# DataDriven_sheet2_nRF9160.net
KiCad netlist of a schematic drawn in Altium Designer
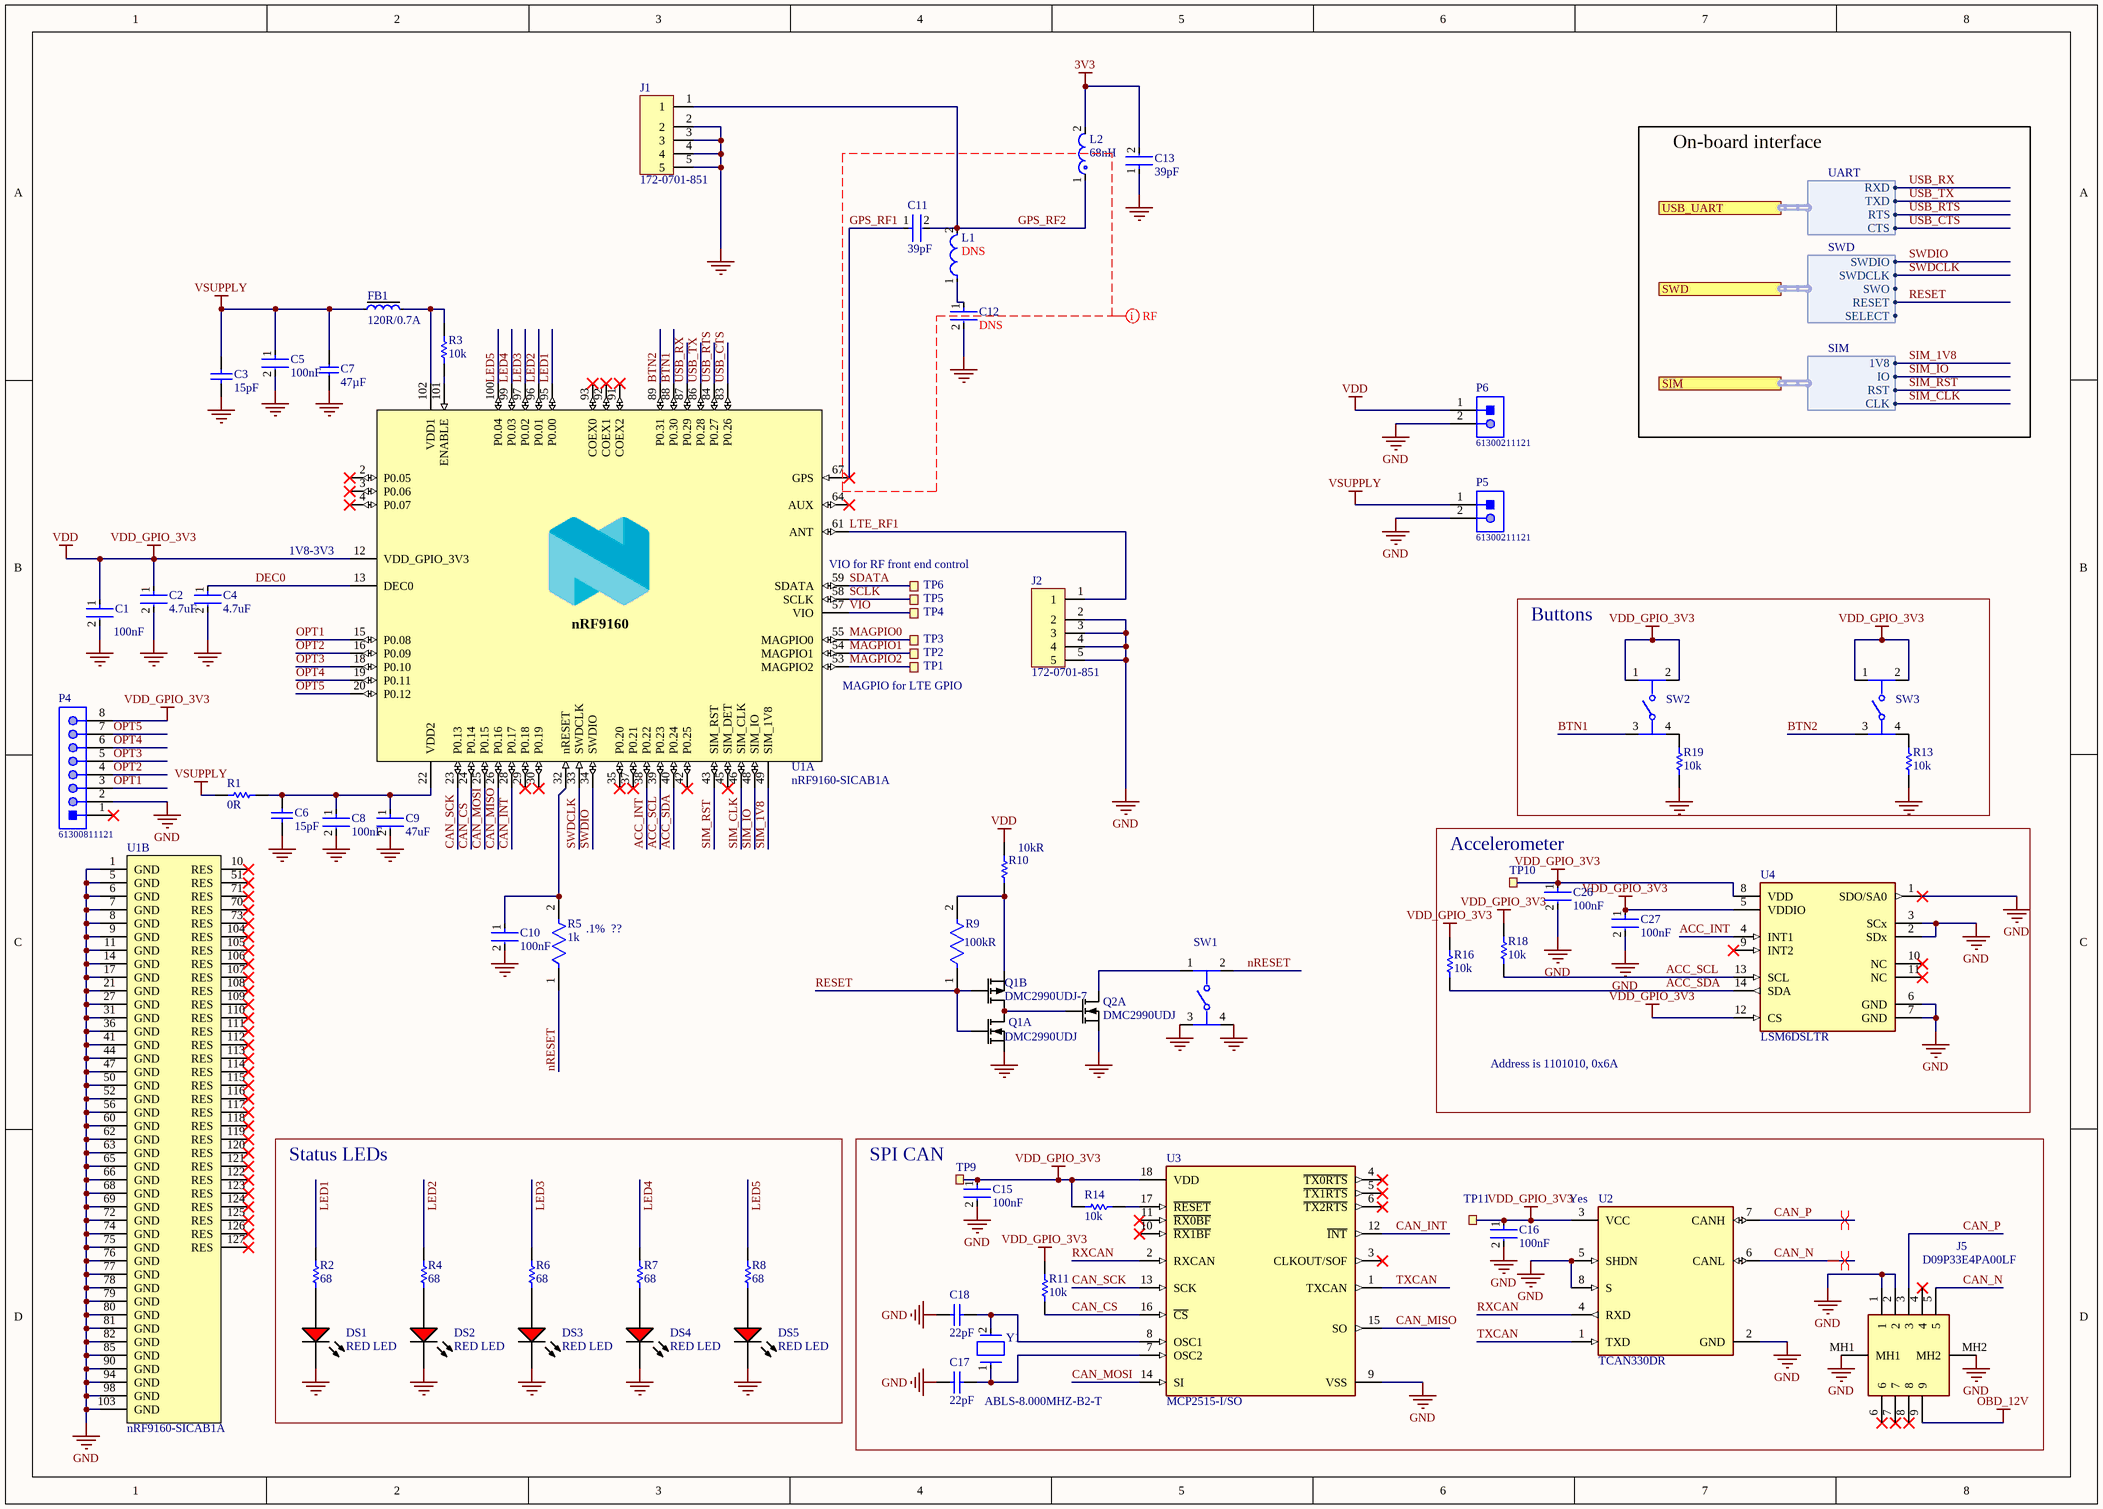
[diagram p0: DataDriven_sheet2_nRF9160.SchDoc]

(export (version "E")
  (design (tool "Eeschema 10.0.6"))
  (components
    (comp (ref "C1")
      (value "100nF")
      (footprint "FP-CGA3E-0_3-0_1-IPC_A")
      (description "Cap Ceramic 100nF 50V X7R 10% Pad SMD 0603 +125°C Automotive T/R")
      (fields (field (name "TOLERANCE") "10%") (field (name "VOLTAGE") "50V"))
      (libsource (lib "Altium Content Vault") (part "b4654b650e69147ec39a6b967a45e02"))
    )
    (comp (ref "C2")
      (value "4.7uF")
      (footprint "FP-C0603-CG-MFG")
      (description "CAP CER 4.7UF 6.3V X5R 0603")
      (fields (field (name "TOLERANCE") "10%") (field (name "MANUFACTURER") "Kemet"))
      (libsource (lib "Altium Content Vault") (part "11868f565c42a9108669ba33697ecf6"))
    )
    (comp (ref "C3")
      (value "15pF")
      (footprint "CAPC1608X90X35ML10T15")
      (description "15 pF ±5% 50V Ceramic Capacitor C0G, NP0 0603 (1608 Metric)")
      (fields (field (name "PART NUMBER") "GRM1885C1H150JA01D") (field (name "MANUFACTURER") "Murata"))
      (libsource (lib "Altium Content Vault") (part "CAP"))
    )
    (comp (ref "C4")
      (value "4.7uF")
      (footprint "FP-C0603-CG-MFG")
      (description "CAP CER 4.7UF 6.3V X5R 0603")
      (fields (field (name "TOLERANCE") "10%") (field (name "MANUFACTURER") "Kemet"))
      (libsource (lib "Altium Content Vault") (part "11868f565c42a9108669ba33697ecf6"))
    )
    (comp (ref "C5")
      (value "100nF")
      (footprint "FP-CGA3E-0_3-0_1-IPC_A")
      (description "Cap Ceramic 100nF 50V X7R 10% Pad SMD 0603 +125°C Automotive T/R")
      (fields (field (name "TOLERANCE") "10%") (field (name "VOLTAGE") "50V"))
      (libsource (lib "Altium Content Vault") (part "b4654b650e69147ec39a6b967a45e02"))
    )
    (comp (ref "C6")
      (value "15pF")
      (footprint "CAPC1608X90X35ML10T15")
      (description "15 pF ±5% 50V Ceramic Capacitor C0G, NP0 0603 (1608 Metric)")
      (fields (field (name "PART NUMBER") "GRM1885C1H150JA01D") (field (name "MANUFACTURER") "Murata"))
      (libsource (lib "Altium Content Vault") (part "CAP"))
    )
    (comp (ref "C7")
      (value "47µF")
      (footprint "pca10090:CAPC2012X11L")
      (description "CAP CER 47UF 10V X5R 0805")
      (fields
        (field (name "PART NUMBER") "C0805-47µ-10V")
        (field (name "MANUFACTURER") "Murata")
        (field (name "AUTHOR") "rsk")
      )
      (libsource (lib "AltiumLib") (part "CAP"))
    )
    (comp (ref "C8")
      (value "100nF")
      (footprint "FP-CGA3E-0_3-0_1-IPC_A")
      (description "Cap Ceramic 100nF 50V X7R 10% Pad SMD 0603 +125°C Automotive T/R")
      (fields (field (name "TOLERANCE") "10%") (field (name "VOLTAGE") "50V"))
      (libsource (lib "Altium Content Vault") (part "b4654b650e69147ec39a6b967a45e02"))
    )
    (comp (ref "C9")
      (value "47uF")
      (footprint "FP-GRM188-0_2-IPC_B")
      (description "Chip Multilayer Ceramic Capacitors for General Purpose, 0603, 47uF, X5R, 15%, 20%, 6.3V")
      (fields (field (name "TOLERANCE") "20%") (field (name "PART NUMBER") "GRM188R60J476ME15D"))
      (libsource (lib "Altium Content Vault") (part "11868f565c42a9108669ba33697ecf6"))
    )
    (comp (ref "C10")
      (value "100nF")
      (footprint "FP-CGA3E-0_3-0_1-IPC_A")
      (description "Cap Ceramic 100nF 50V X7R 10% Pad SMD 0603 +125°C Automotive T/R")
      (fields (field (name "TOLERANCE") "10%") (field (name "VOLTAGE") "50V"))
      (libsource (lib "Altium Content Vault") (part "b4654b650e69147ec39a6b967a45e02"))
    )
    (comp (ref "C11")
      (value "39pF")
      (footprint "FP-C0603C-CF-MFG")
      (description "CAP CER 39PF 50V 5% NP0 0603")
      (fields
        (field (name "OCTOPART") "https://octopart.com/c0603c390j5gactu-kemet-8375739")
        (field (name "MANUFACTURER PART NUMBER") "C0603C390J5GACTU")
      )
      (libsource (lib "Altium Content Vault") (part "b4654b650e69147ec39a6b967a45e02"))
    )
    (comp (ref "C12")
      (value "DNS")
      (footprint "FP-CGA3E-0_3-0_1-IPC_A")
      (description "Cap Ceramic 100nF 50V X7R 10% Pad SMD 0603 +125°C Automotive T/R")
      (fields (field (name "TOLERANCE") "10%") (field (name "VOLTAGE") "50V"))
      (libsource (lib "Altium Content Vault") (part "b4654b650e69147ec39a6b967a45e02"))
    )
    (comp (ref "C13")
      (value "39pF")
      (footprint "FP-C0603C-CF-MFG")
      (description "CAP CER 39PF 50V 5% NP0 0603")
      (fields
        (field (name "OCTOPART") "https://octopart.com/c0603c390j5gactu-kemet-8375739")
        (field (name "MANUFACTURER PART NUMBER") "C0603C390J5GACTU")
      )
      (libsource (lib "Altium Content Vault") (part "b4654b650e69147ec39a6b967a45e02"))
    )
    (comp (ref "C15")
      (value "100nF")
      (footprint "FP-CGA3E-0_3-0_1-IPC_A")
      (description "Cap Ceramic 100nF 50V X7R 10% Pad SMD 0603 +125°C Automotive T/R")
      (fields (field (name "TOLERANCE") "10%") (field (name "VOLTAGE") "50V"))
      (libsource (lib "Altium Content Vault") (part "b4654b650e69147ec39a6b967a45e02"))
    )
    (comp (ref "C16")
      (value "100nF")
      (footprint "FP-CGA3E-0_3-0_1-IPC_A")
      (description "Cap Ceramic 100nF 50V X7R 10% Pad SMD 0603 +125°C Automotive T/R")
      (fields (field (name "TOLERANCE") "10%") (field (name "VOLTAGE") "50V"))
      (libsource (lib "Altium Content Vault") (part "b4654b650e69147ec39a6b967a45e02"))
    )
    (comp (ref "C17")
      (value "22pF")
      (footprint "CAPC1608X90X35ML10T15")
      (description "Chip Capacitor, 22 pF, +/- 5%, 50 V, -55 to 125 degC, 0603 (1608 Metric), RoHS, Tape and Reel")
      (fields
        (field (name "MANUFACTURER") "Murata")
        (field (name "MANUFACTURER PART NUMBER") "GRM1885C1H220JA01D")
      )
      (libsource (lib "Altium Content Vault") (part "CAP-NP-2"))
    )
    (comp (ref "C18")
      (value "22pF")
      (footprint "CAPC1608X90X35ML10T15")
      (description "Chip Capacitor, 22 pF, +/- 5%, 50 V, -55 to 125 degC, 0603 (1608 Metric), RoHS, Tape and Reel")
      (fields
        (field (name "MANUFACTURER") "Murata")
        (field (name "MANUFACTURER PART NUMBER") "GRM1885C1H220JA01D")
      )
      (libsource (lib "Altium Content Vault") (part "CAP-NP-2"))
    )
    (comp (ref "C26")
      (value "100nF")
      (footprint "FP-CGA3E-0_3-0_1-IPC_A")
      (description "Cap Ceramic 100nF 50V X7R 10% Pad SMD 0603 +125°C Automotive T/R")
      (fields (field (name "TOLERANCE") "10%") (field (name "VOLTAGE") "50V"))
      (libsource (lib "Altium Content Vault") (part "b4654b650e69147ec39a6b967a45e02"))
    )
    (comp (ref "C27")
      (value "100nF")
      (footprint "FP-CGA3E-0_3-0_1-IPC_A")
      (description "Cap Ceramic 100nF 50V X7R 10% Pad SMD 0603 +125°C Automotive T/R")
      (fields (field (name "TOLERANCE") "10%") (field (name "VOLTAGE") "50V"))
      (libsource (lib "Altium Content Vault") (part "b4654b650e69147ec39a6b967a45e02"))
    )
    (comp (ref "DS1")
      (value "RED LED")
      (footprint "VISH-TLMX1100_V")
      (description "LED, RED, 2.1 V, -40 to 100 degC, 2-Pin SMD (0603), RoHS, Tape and Reel")
      (fields (field (name "TOLERANCE") "5%") (field (name "PART NUMBER") "TLMS1100-GS08"))
      (libsource (lib "Altium Content Vault") (part "LED-RED-AK-2"))
    )
    (comp (ref "DS2")
      (value "RED LED")
      (footprint "VISH-TLMX1100_V")
      (description "LED, RED, 2.1 V, -40 to 100 degC, 2-Pin SMD (0603), RoHS, Tape and Reel")
      (fields (field (name "TOLERANCE") "5%") (field (name "MANUFACTURER") "Vishay"))
      (libsource (lib "Altium Content Vault") (part "LED-RED-AK-2"))
    )
    (comp (ref "DS3")
      (value "RED LED")
      (footprint "VISH-TLMX1100_V")
      (description "LED, RED, 2.1 V, -40 to 100 degC, 2-Pin SMD (0603), RoHS, Tape and Reel")
      (fields (field (name "TOLERANCE") "5%") (field (name "MANUFACTURER") "Vishay"))
      (libsource (lib "Altium Content Vault") (part "LED-RED-AK-2"))
    )
    (comp (ref "DS4")
      (value "RED LED")
      (footprint "VISH-TLMX1100_V")
      (description "LED, RED, 2.1 V, -40 to 100 degC, 2-Pin SMD (0603), RoHS, Tape and Reel")
      (fields (field (name "TOLERANCE") "5%") (field (name "MANUFACTURER") "Vishay"))
      (libsource (lib "Altium Content Vault") (part "LED-RED-AK-2"))
    )
    (comp (ref "DS5")
      (value "RED LED")
      (footprint "VISH-TLMX1100_V")
      (description "LED, RED, 2.1 V, -40 to 100 degC, 2-Pin SMD (0603), RoHS, Tape and Reel")
      (fields (field (name "TOLERANCE") "5%") (field (name "MANUFACTURER") "Vishay"))
      (libsource (lib "Altium Content Vault") (part "LED-RED-AK-2"))
    )
    (comp (ref "FB1")
      (value "120R/0.7A")
      (footprint "pca10090:INDC1005X04L")
      (description "Ferrite Bead, 120 Ohm @ 100MHz, 700mA, 130 mOhm Max")
      (fields
        (field (name "PART NUMBER") "FB0402-120R@100M-700mA")
        (field (name "MANUFACTURER") "Murata")
        (field (name "AUTHOR") "rsk")
      )
      (libsource (lib "AltiumLib") (part "IND_F"))
    )
    (comp (ref "J1")
      (value "172-0701-851")
      (footprint "DataDriven_PCB1:142-0701-851")
      (description "SMA Connector Jack, Female Socket 50Ohm Board Edge, End Launch Solder Tab")
      (fields
        (field (name "MANUFACTURER") "Cinch Connectivity Solutions Johnson")
        (field (name "MANUFACTURER PART NUMBER") "142-0701-851")
      )
      (libsource (lib "DataDriven") (part "172-0701-851"))
    )
    (comp (ref "J2")
      (value "172-0701-851")
      (footprint "DataDriven_PCB1:142-0701-851")
      (description "SMA Connector Jack, Female Socket 50Ohm Board Edge, End Launch Solder Tab")
      (fields
        (field (name "MANUFACTURER") "Cinch Connectivity Solutions Johnson")
        (field (name "MANUFACTURER PART NUMBER") "142-0701-851")
      )
      (libsource (lib "DataDriven") (part "172-0701-851"))
    )
    (comp (ref "J5")
      (value "D09P33E4PA00LF")
      (footprint "DataDriven_PCB1:D09P33E4PA00LF")
      (description "D-Sub Standard Connectors 9P RA PIN SOLDER SHELL SIZE E")
      (fields
        (field (name "MOUSER PART NUMBER") "649-D09P33E4PA00LF")
        (field (name "MANUFACTURER") "Amphenol FCI")
      )
      (libsource (lib "DataDriven") (part "D09P33E4PA00LF"))
    )
    (comp (ref "L1")
      (value "DNS")
      (footprint "FP-LQW18AN_00-MFG")
      (description "Wire Wound RF Inductor 9.1nH ±0.5nH 650mA 0.11Ω 0603 (1608)")
      (fields (field (name "TOLERANCE") "5%") (field (name "MANUFACTURER") "Murata"))
      (libsource (lib "Altium Content Vault") (part "725321dda6339637d4d059423bc1c3c"))
    )
    (comp (ref "L2")
      (value "68nH")
      (footprint "FP-LQG18HH_00-MFG")
      (description "Multilayer type RF Inductor 68nH ±5% 0.8Ω 400mA 0603")
      (fields (field (name "TOLERANCE") "5%") (field (name "MANUFACTURER") "Murata"))
      (libsource (lib "Altium Content Vault") (part "4cc4b267dca4c8e51f7102f422741d8"))
    )
    (comp (ref "P4")
      (value "61300811121")
      (footprint "61300811121")
      (description "THT Vertical Pin Header WR-PHD, Pitch 2.54 mm, Single Row, 8 pins")
      (fields (field (name "MANUFACTURER") "Wurth Elektronik") (field (name "PUBLISHER") "WurthElektronik"))
      (libsource (lib "Altium Content Vault") (part "WE-CN-1P-M-R8"))
    )
    (comp (ref "P5")
      (value "61300211121")
      (footprint "61300211121")
      (description "THT Vertical Pin Header WR-PHD, Pitch 2.54 mm, Single Row, 2 pins")
      (fields (field (name "MANUFACTURER") "Wurth Elektronik") (field (name "PUBLISHER") "WurthElektronik"))
      (libsource (lib "Altium Content Vault") (part "WE-CN-1P-M-R2"))
    )
    (comp (ref "P6")
      (value "61300211121")
      (footprint "61300211121")
      (description "THT Vertical Pin Header WR-PHD, Pitch 2.54 mm, Single Row, 2 pins")
      (fields (field (name "MANUFACTURER") "Wurth Elektronik") (field (name "PUBLISHER") "WurthElektronik"))
      (libsource (lib "Altium Content Vault") (part "WE-CN-1P-M-R2"))
    )
    (comp (ref "Q1")
      (value "DMC2990UDJ")
      (footprint "pca10090:SOTFL35P100X50-6N")
      (description "MOSFET, Dual N and P-Channel, 20V, 450mA/310mA, 990mOhm, 350mW")
      (fields
        (field (name "PART NUMBER") "DMC2990UDJ-7")
        (field (name "MANUFACTURER") "Diodes Incorporated")
        (field (name "AUTHOR") "rsk")
      )
      (libsource (lib "AltiumLib") (part "T{colon}FET-N/P-DUAL"))
    )
    (comp (ref "Q2")
      (value "DMC2990UDJ")
      (footprint "pca10090:SOTFL35P100X50-6N")
      (description "MOSFET, Dual N and P-Channel, 20V, 450mA/310mA, 990mOhm, 350mW")
      (fields
        (field (name "PART NUMBER") "DMC2990UDJ-7")
        (field (name "MANUFACTURER") "Diodes Incorporated")
        (field (name "AUTHOR") "rsk")
      )
      (libsource (lib "AltiumLib") (part "T{colon}FET-N/P-DUAL"))
    )
    (comp (ref "R1")
      (value "0R")
      (footprint "RESC1608X55X25ML10T15")
      (description "Chip Resistor, 0 Ohm, +/- 5%, 0.1 W, -55 to 155 degC, 0603 (1608 Metric), RoHS, Tape and Reel")
      (fields (field (name "TOLERANCE") "5%") (field (name "MANUFACTURER") "Yageo"))
      (libsource (lib "Altium Content Vault") (part "RES-2"))
    )
    (comp (ref "R2")
      (value "68")
      (footprint "RESC1608X55X30ML15T15")
      (description "68 Ohms ±1% 0.1W, 1/10W Chip Resistor 0603 (1608 Metric) Automotive AEC-Q200 Thick Film")
      (fields (field (name "MANUFACTURER") "Panasonic") (field (name "PART NUMBER") "ERJ-3EKF68R0V"))
      (libsource (lib "Altium Content Vault") (part "RES"))
    )
    (comp (ref "R3")
      (value "10k")
      (footprint "RESC1609X50X30NL8T20")
      (description "Chip Resistor, 10 KOhm, +/- 1%, 100 mW, -55 to 155 degC, 0603 (1608 Metric), RoHS, Tape and Reel")
      (fields
        (field (name "MANUFACTURER") "Vishay Semiconductor")
        (field (name "MANUFACTURER PART NUMBER") "CRCW060310K0FKEA")
      )
      (libsource (lib "Altium Content Vault") (part "RES-2"))
    )
    (comp (ref "R4")
      (value "68")
      (footprint "RESC1608X55X30ML15T15")
      (description "68 Ohms ±1% 0.1W, 1/10W Chip Resistor 0603 (1608 Metric) Automotive AEC-Q200 Thick Film")
      (fields (field (name "MANUFACTURER") "Panasonic") (field (name "PART NUMBER") "ERJ-3EKF68R0V"))
      (libsource (lib "Altium Content Vault") (part "RES"))
    )
    (comp (ref "R5")
      (value "1k")
      (footprint "FP-ERA3A-IPC_C")
      (description "RES SMD 1K OHM 0.1% 1/10W 0603")
      (fields (field (name "TOLERANCE") "0.1%") (field (name "MANUFACTURER") "Panasonic"))
      (libsource (lib "Altium Content Vault") (part "1029c3af85768c4190bb7ad29bc67b5"))
    )
    (comp (ref "R6")
      (value "68")
      (footprint "RESC1608X55X30ML15T15")
      (description "68 Ohms ±1% 0.1W, 1/10W Chip Resistor 0603 (1608 Metric) Automotive AEC-Q200 Thick Film")
      (fields (field (name "MANUFACTURER") "Panasonic") (field (name "PART NUMBER") "ERJ-3EKF68R0V"))
      (libsource (lib "Altium Content Vault") (part "RES"))
    )
    (comp (ref "R7")
      (value "68")
      (footprint "RESC1608X55X30ML15T15")
      (description "68 Ohms ±1% 0.1W, 1/10W Chip Resistor 0603 (1608 Metric) Automotive AEC-Q200 Thick Film")
      (fields (field (name "MANUFACTURER") "Panasonic") (field (name "PART NUMBER") "ERJ-3EKF68R0V"))
      (libsource (lib "Altium Content Vault") (part "RES"))
    )
    (comp (ref "R8")
      (value "68")
      (footprint "RESC1608X55X30ML15T15")
      (description "68 Ohms ±1% 0.1W, 1/10W Chip Resistor 0603 (1608 Metric) Automotive AEC-Q200 Thick Film")
      (fields (field (name "MANUFACTURER") "Panasonic") (field (name "PART NUMBER") "ERJ-3EKF68R0V"))
      (libsource (lib "Altium Content Vault") (part "RES"))
    )
    (comp (ref "R9")
      (value "RC0603FR-07100KL")
      (footprint "FP-RC0603-0_55-MFG")
      (description "RES SMD 100K OHM 1% 1/10W 0603")
      (fields
        (field (name "RESISTANCE") "100kR")
        (field (name "TOLERANCE") "1%")
        (field (name "MANUFACTURER") "Yaego")
      )
      (libsource (lib "Altium Content Vault") (part "1029c3af85768c4190bb7ad29bc67b5"))
    )
    (comp (ref "R10")
      (value "10kR")
      (footprint "RESC1609X50X30NL8T20")
      (description "Chip Resistor, 10 KOhm, +/- 1%, 100 mW, -55 to 155 degC, 0603 (1608 Metric), RoHS, Tape and Reel")
      (fields (field (name "MANUFACTURER") "Vishay Semiconductor") (field (name "TOLERANCE") "1%"))
      (libsource (lib "Altium Content Vault") (part "RES-2"))
    )
    (comp (ref "R11")
      (value "10k")
      (footprint "RESC1609X50X30NL8T20")
      (description "Chip Resistor, 10 KOhm, +/- 1%, 100 mW, -55 to 155 degC, 0603 (1608 Metric), RoHS, Tape and Reel")
      (fields
        (field (name "MANUFACTURER") "Vishay Semiconductor")
        (field (name "MANUFACTURER PART NUMBER") "CRCW060310K0FKEA")
      )
      (libsource (lib "Altium Content Vault") (part "RES-2"))
    )
    (comp (ref "R13")
      (value "10k")
      (footprint "RESC1609X50X30NL8T20")
      (description "Chip Resistor, 10 KOhm, +/- 1%, 100 mW, -55 to 155 degC, 0603 (1608 Metric), RoHS, Tape and Reel")
      (fields
        (field (name "MANUFACTURER") "Vishay Semiconductor")
        (field (name "MANUFACTURER PART NUMBER") "CRCW060310K0FKEA")
      )
      (libsource (lib "Altium Content Vault") (part "RES-2"))
    )
    (comp (ref "R14")
      (value "10k")
      (footprint "RESC1609X50X30NL8T20")
      (description "Chip Resistor, 10 KOhm, +/- 1%, 100 mW, -55 to 155 degC, 0603 (1608 Metric), RoHS, Tape and Reel")
      (fields
        (field (name "MANUFACTURER") "Vishay Semiconductor")
        (field (name "MANUFACTURER PART NUMBER") "CRCW060310K0FKEA")
      )
      (libsource (lib "Altium Content Vault") (part "RES-2"))
    )
    (comp (ref "R16")
      (value "10k")
      (footprint "RESC1609X50X30NL8T20")
      (description "Chip Resistor, 10 KOhm, +/- 1%, 100 mW, -55 to 155 degC, 0603 (1608 Metric), RoHS, Tape and Reel")
      (fields
        (field (name "MANUFACTURER") "Vishay Semiconductor")
        (field (name "MANUFACTURER PART NUMBER") "CRCW060310K0FKEA")
      )
      (libsource (lib "Altium Content Vault") (part "RES-2"))
    )
    (comp (ref "R18")
      (value "10k")
      (footprint "RESC1609X50X30NL8T20")
      (description "Chip Resistor, 10 KOhm, +/- 1%, 100 mW, -55 to 155 degC, 0603 (1608 Metric), RoHS, Tape and Reel")
      (fields
        (field (name "MANUFACTURER") "Vishay Semiconductor")
        (field (name "MANUFACTURER PART NUMBER") "CRCW060310K0FKEA")
      )
      (libsource (lib "Altium Content Vault") (part "RES-2"))
    )
    (comp (ref "R19")
      (value "10k")
      (footprint "RESC1609X50X30NL8T20")
      (description "Chip Resistor, 10 KOhm, +/- 1%, 100 mW, -55 to 155 degC, 0603 (1608 Metric), RoHS, Tape and Reel")
      (fields
        (field (name "MANUFACTURER") "Vishay Semiconductor")
        (field (name "MANUFACTURER PART NUMBER") "CRCW060310K0FKEA")
      )
      (libsource (lib "Altium Content Vault") (part "RES-2"))
    )
    (comp (ref "SW1")
      (value "~")
      (footprint "FP-PTS645SM43SMTR92LFS-MFG")
      (description "SWITCH TACTILE SPST-NO 0.05A 12V")
      (fields
        (field (name "MANUFACTURER") "ITT C&K")
        (field (name "MANUFACTURER PART NUMBER") "PTS645SM43SMTR92LFS")
      )
      (libsource (lib "Altium Content Vault") (part "1adf0dd01260c80cf25a44bfd6b99ba"))
    )
    (comp (ref "SW2")
      (value "~")
      (footprint "FP-PTS645SM43SMTR92LFS-MFG")
      (description "SWITCH TACTILE SPST-NO 0.05A 12V")
      (fields
        (field (name "MANUFACTURER") "ITT C&K")
        (field (name "MANUFACTURER PART NUMBER") "PTS645SM43SMTR92LFS")
      )
      (libsource (lib "Altium Content Vault") (part "1adf0dd01260c80cf25a44bfd6b99ba"))
    )
    (comp (ref "SW3")
      (value "~")
      (footprint "FP-PTS645SM43SMTR92LFS-MFG")
      (description "SWITCH TACTILE SPST-NO 0.05A 12V")
      (fields
        (field (name "MANUFACTURER") "ITT C&K")
        (field (name "MANUFACTURER PART NUMBER") "PTS645SM43SMTR92LFS")
      )
      (libsource (lib "Altium Content Vault") (part "1adf0dd01260c80cf25a44bfd6b99ba"))
    )
    (comp (ref "TP1")
      (value "Ø1.0mm,SMD")
      (footprint "pca10090:TP_SMD_D1.0mm")
      (description "1.0mm circular SMD testpad")
      (fields
        (field (name "PART NUMBER") "TP_SMD_Ø1.0MM")
        (field (name "MANUFACTURER") "Nordic Semiconductor")
        (field (name "AUTHOR") "rsk")
      )
      (libsource (lib "AltiumLib") (part "TESTPAD"))
    )
    (comp (ref "TP2")
      (value "Ø1.0mm,SMD")
      (footprint "pca10090:TP_SMD_D1.0mm")
      (description "1.0mm circular SMD testpad")
      (fields
        (field (name "PART NUMBER") "TP_SMD_Ø1.0MM")
        (field (name "MANUFACTURER") "Nordic Semiconductor")
        (field (name "AUTHOR") "rsk")
      )
      (libsource (lib "AltiumLib") (part "TESTPAD"))
    )
    (comp (ref "TP3")
      (value "Ø1.0mm,SMD")
      (footprint "pca10090:TP_SMD_D1.0mm")
      (description "1.0mm circular SMD testpad")
      (fields
        (field (name "PART NUMBER") "TP_SMD_Ø1.0MM")
        (field (name "MANUFACTURER") "Nordic Semiconductor")
        (field (name "AUTHOR") "rsk")
      )
      (libsource (lib "AltiumLib") (part "TESTPAD"))
    )
    (comp (ref "TP4")
      (value "Ø1.0mm,SMD")
      (footprint "pca10090:TP_SMD_D1.0mm")
      (description "1.0mm circular SMD testpad")
      (fields
        (field (name "PART NUMBER") "TP_SMD_Ø1.0MM")
        (field (name "MANUFACTURER") "Nordic Semiconductor")
        (field (name "AUTHOR") "rsk")
      )
      (libsource (lib "AltiumLib") (part "TESTPAD"))
    )
    (comp (ref "TP5")
      (value "Ø1.0mm,SMD")
      (footprint "pca10090:TP_SMD_D1.0mm")
      (description "1.0mm circular SMD testpad")
      (fields
        (field (name "PART NUMBER") "TP_SMD_Ø1.0MM")
        (field (name "MANUFACTURER") "Nordic Semiconductor")
        (field (name "AUTHOR") "rsk")
      )
      (libsource (lib "AltiumLib") (part "TESTPAD"))
    )
    (comp (ref "TP6")
      (value "Ø1.0mm,SMD")
      (footprint "pca10090:TP_SMD_D1.0mm")
      (description "1.0mm circular SMD testpad")
      (fields
        (field (name "PART NUMBER") "TP_SMD_Ø1.0MM")
        (field (name "MANUFACTURER") "Nordic Semiconductor")
        (field (name "AUTHOR") "rsk")
      )
      (libsource (lib "AltiumLib") (part "TESTPAD"))
    )
    (comp (ref "TP9")
      (value "Ø1.0mm,SMD")
      (footprint "pca10090:TP_SMD_D1.0mm")
      (description "1.0mm circular SMD testpad")
      (fields
        (field (name "PART NUMBER") "TP_SMD_Ø1.0MM")
        (field (name "MANUFACTURER") "Nordic Semiconductor")
        (field (name "AUTHOR") "rsk")
      )
      (libsource (lib "") (part "TESTPAD_1"))
    )
    (comp (ref "TP10")
      (value "Ø1.0mm,SMD")
      (footprint "pca10090:TP_SMD_D1.0mm")
      (description "1.0mm circular SMD testpad")
      (fields
        (field (name "PART NUMBER") "TP_SMD_Ø1.0MM")
        (field (name "MANUFACTURER") "Nordic Semiconductor")
        (field (name "AUTHOR") "rsk")
      )
      (libsource (lib "") (part "TESTPAD_1"))
    )
    (comp (ref "TP11")
      (value "Ø1.0mm,SMD")
      (footprint "pca10090:TP_SMD_D1.0mm")
      (description "1.0mm circular SMD testpad")
      (fields
        (field (name "PART NUMBER") "TP_SMD_Ø1.0MM")
        (field (name "MANUFACTURER") "Nordic Semiconductor")
        (field (name "AUTHOR") "rsk")
      )
      (libsource (lib "") (part "TESTPAD_1"))
    )
    (comp (ref "U1")
      (value "nRF9160-SICAB1A")
      (footprint "pca10090:LGA50P1600X1050X104-161N")
      (description "Low power System-in-Package with integrated LTE-M/NB-IoT modem and GPS")
      (fields (field (name "MANUFACTURER") "Nordic Semiconductor") (field (name "AUTHOR") "rsk"))
      (libsource (lib "AltiumLib") (part "nRF9160_SICA"))
    )
    (comp (ref "U2")
      (value "TCAN330DR")
      (footprint "FP-D0008A-IPC_B")
      (description "IC TRANSCEIVER 1/1 8SOIC")
      (fields (field (name "ROHS COMPLIANT") "Yes") (field (name "MANUFACTURER") "Texas Instruments"))
      (libsource (lib "Altium Content Vault") (part "2cff83dcd93ccda1ab41292df9c405d"))
    )
    (comp (ref "U3")
      (value "MCP2515-I/SO")
      (footprint "FP-C04-051-MFG")
      (description "IC CAN CONTROLLER W/SPI 18SOIC")
      (fields
        (field (name "MANUFACTURER") "Microchip")
        (field (name "OCTOPART") "https://octopart.com/mcp2515-i%2Fso-microchip-430187")
      )
      (libsource (lib "Altium Content Vault") (part "1c78ea6ff576bac94664e2637e1b479"))
    )
    (comp (ref "U4")
      (value "LSM6DSLTR")
      (footprint "FP-LGA-14L-DM00249496-MFG")
      (description "IMU ACCEL/GYRO I2C/SPI 14LGA")
      (fields
        (field (name "MANUFACTURER") "STMicroelectronics")
        (field (name "OCTOPART") "https://octopart.com/lsm6dsltr-stmicroelectronics-66358193")
      )
      (libsource (lib "Altium Content Vault") (part "4e27e7d1829efda5344af1708d65448"))
    )
    (comp (ref "Y1")
      (value "ABLS-8.000MHZ-B2-T")
      (footprint "FP-ABLS-MFG")
      (description "CRYSTAL 8.0000MHZ 18PF SMD")
      (fields (field (name "TOLERANCE") "20ppm") (field (name "MANUFACTURER") "Abracon LLC"))
      (libsource (lib "Altium Content Vault") (part "c23a69dc6c9e2f18f2079038eb95dd1"))
    )
  )
  (nets
    (net (code "4") (name "/ACC_INT") (class "Default")
      (node (ref "U1") (pin "38") (pinfunction "P0.22_38") (pintype "bidirectional"))
      (node (ref "U4") (pin "4") (pinfunction "INT1_4") (pintype "input"))
    )
    (net (code "5") (name "/ACC_SCL") (class "Default")
      (node (ref "R18") (pin "1") (pinfunction "1_1") (pintype "passive"))
      (node (ref "U1") (pin "39") (pinfunction "P0.23_39") (pintype "bidirectional"))
      (node (ref "U4") (pin "13") (pinfunction "SCL_13") (pintype "input"))
    )
    (net (code "6") (name "/ACC_SDA") (class "Default")
      (node (ref "R16") (pin "1") (pinfunction "1_1") (pintype "passive"))
      (node (ref "U1") (pin "40") (pinfunction "P0.24_40") (pintype "bidirectional"))
      (node (ref "U4") (pin "14") (pinfunction "SDA_14") (pintype "output"))
    )
    (net (code "7") (name "/BTN1") (class "Default")
      (node (ref "SW2") (pin "3") (pinfunction "3_3") (pintype "passive"))
      (node (ref "U1") (pin "88") (pinfunction "P0.30_88") (pintype "bidirectional"))
    )
    (net (code "8") (name "/BTN2") (class "Default")
      (node (ref "SW3") (pin "3") (pinfunction "3_3") (pintype "passive"))
      (node (ref "U1") (pin "89") (pinfunction "P0.31_89") (pintype "bidirectional"))
    )
    (net (code "9") (name "/CAN_CS") (class "Default")
      (node (ref "R11") (pin "2") (pinfunction "2_2") (pintype "passive"))
      (node (ref "U1") (pin "24") (pinfunction "P0.14_24") (pintype "bidirectional"))
      (node (ref "U3") (pin "16") (pinfunction "~{CS}_16") (pintype "input"))
    )
    (net (code "10") (name "/CAN_INT") (class "Default")
      (node (ref "U1") (pin "28") (pinfunction "P0.17_28") (pintype "bidirectional"))
      (node (ref "U3") (pin "12") (pinfunction "~{INT}_12") (pintype "output"))
    )
    (net (code "11") (name "/CAN_MISO") (class "Default")
      (node (ref "U1") (pin "26") (pinfunction "P0.16_26") (pintype "bidirectional"))
      (node (ref "U3") (pin "15") (pinfunction "SO_15") (pintype "output"))
    )
    (net (code "12") (name "/CAN_MOSI") (class "Default")
      (node (ref "U1") (pin "25") (pinfunction "P0.15_25") (pintype "bidirectional"))
      (node (ref "U3") (pin "14") (pinfunction "SI_14") (pintype "input"))
    )
    (net (code "13") (name "/CAN_N") (class "Default")
      (node (ref "J5") (pin "5") (pinfunction "5_5") (pintype "passive"))
      (node (ref "U2") (pin "6") (pinfunction "CANL_6") (pintype "bidirectional"))
    )
    (net (code "14") (name "/CAN_P") (class "Default")
      (node (ref "J5") (pin "3") (pinfunction "3_3") (pintype "passive"))
      (node (ref "U2") (pin "7") (pinfunction "CANH_7") (pintype "bidirectional"))
    )
    (net (code "15") (name "/CAN_SCK") (class "Default")
      (node (ref "U1") (pin "23") (pinfunction "P0.13_23") (pintype "bidirectional"))
      (node (ref "U3") (pin "13") (pinfunction "SCK_13") (pintype "input"))
    )
    (net (code "16") (name "/DEC0") (class "Default")
      (node (ref "C4") (pin "1") (pinfunction "1_1") (pintype "passive"))
      (node (ref "U1") (pin "13") (pinfunction "DEC0_13") (pintype "power_in"))
    )
    (net (code "17") (name "/GPS_RF1") (class "Default")
      (node (ref "C11") (pin "1") (pinfunction "1_1") (pintype "passive"))
      (node (ref "U1") (pin "67") (pinfunction "GPS_67") (pintype "input"))
    )
    (net (code "18") (name "/GPS_RF2") (class "Default")
      (node (ref "C11") (pin "2") (pinfunction "2_2") (pintype "passive"))
      (node (ref "J1") (pin "1") (pinfunction "1_1") (pintype "passive"))
      (node (ref "L1") (pin "2") (pinfunction "2_2") (pintype "passive"))
      (node (ref "L2") (pin "1") (pinfunction "1_1") (pintype "passive"))
    )
    (net (code "19") (name "/LED1") (class "Default")
      (node (ref "R2") (pin "2") (pinfunction "2_2") (pintype "passive"))
      (node (ref "U1") (pin "95") (pinfunction "P0.00_95") (pintype "bidirectional"))
    )
    (net (code "20") (name "/LED2") (class "Default")
      (node (ref "R4") (pin "2") (pinfunction "2_2") (pintype "passive"))
      (node (ref "U1") (pin "96") (pinfunction "P0.01_96") (pintype "bidirectional"))
    )
    (net (code "21") (name "/LED3") (class "Default")
      (node (ref "R6") (pin "2") (pinfunction "2_2") (pintype "passive"))
      (node (ref "U1") (pin "97") (pinfunction "P0.02_97") (pintype "bidirectional"))
    )
    (net (code "22") (name "/LED4") (class "Default")
      (node (ref "R7") (pin "2") (pinfunction "2_2") (pintype "passive"))
      (node (ref "U1") (pin "99") (pinfunction "P0.03_99") (pintype "bidirectional"))
    )
    (net (code "23") (name "/LED5") (class "Default")
      (node (ref "R8") (pin "2") (pinfunction "2_2") (pintype "passive"))
      (node (ref "U1") (pin "100") (pinfunction "P0.04_100") (pintype "bidirectional"))
    )
    (net (code "24") (name "/LTE_RF1") (class "Default")
      (node (ref "J2") (pin "1") (pinfunction "1_1") (pintype "passive"))
      (node (ref "U1") (pin "61") (pinfunction "ANT_61") (pintype "bidirectional"))
    )
    (net (code "25") (name "/MAGPIO0") (class "Default")
      (node (ref "TP3") (pin "1") (pinfunction "1_1") (pintype "passive"))
      (node (ref "U1") (pin "55") (pinfunction "MAGPIO0_55") (pintype "bidirectional"))
    )
    (net (code "26") (name "/MAGPIO1") (class "Default")
      (node (ref "TP2") (pin "1") (pinfunction "1_1") (pintype "passive"))
      (node (ref "U1") (pin "54") (pinfunction "MAGPIO1_54") (pintype "bidirectional"))
    )
    (net (code "27") (name "/MAGPIO2") (class "Default")
      (node (ref "TP1") (pin "1") (pinfunction "1_1") (pintype "passive"))
      (node (ref "U1") (pin "53") (pinfunction "MAGPIO2_53") (pintype "bidirectional"))
    )
    (net (code "28") (name "/OPT1") (class "Default")
      (node (ref "P4") (pin "3") (pinfunction "3_3") (pintype "passive"))
      (node (ref "U1") (pin "15") (pinfunction "P0.08_15") (pintype "bidirectional"))
    )
    (net (code "29") (name "/OPT2") (class "Default")
      (node (ref "P4") (pin "4") (pinfunction "4_4") (pintype "passive"))
      (node (ref "U1") (pin "16") (pinfunction "P0.09_16") (pintype "bidirectional"))
    )
    (net (code "30") (name "/OPT3") (class "Default")
      (node (ref "P4") (pin "5") (pinfunction "5_5") (pintype "passive"))
      (node (ref "U1") (pin "18") (pinfunction "P0.10_18") (pintype "bidirectional"))
    )
    (net (code "31") (name "/OPT4") (class "Default")
      (node (ref "P4") (pin "6") (pinfunction "6_6") (pintype "passive"))
      (node (ref "U1") (pin "19") (pinfunction "P0.11_19") (pintype "bidirectional"))
    )
    (net (code "32") (name "/OPT5") (class "Default")
      (node (ref "P4") (pin "7") (pinfunction "7_7") (pintype "passive"))
      (node (ref "U1") (pin "20") (pinfunction "P0.12_20") (pintype "bidirectional"))
    )
    (net (code "33") (name "/RESET") (class "Default")
      (node (ref "Q1") (pin "2") (pinfunction "G1_2") (pintype "passive"))
      (node (ref "Q1") (pin "5") (pinfunction "G2_5") (pintype "passive"))
      (node (ref "R9") (pin "1") (pinfunction "1_1") (pintype "passive"))
    )
    (net (code "34") (name "/RXCAN") (class "Default")
      (node (ref "U2") (pin "4") (pinfunction "RXD_4") (pintype "output"))
      (node (ref "U3") (pin "2") (pinfunction "RXCAN_2") (pintype "input"))
    )
    (net (code "35") (name "/SCLK") (class "Default")
      (node (ref "TP5") (pin "1") (pinfunction "1_1") (pintype "passive"))
      (node (ref "U1") (pin "58") (pinfunction "SCLK_58") (pintype "bidirectional"))
    )
    (net (code "36") (name "/SDATA") (class "Default")
      (node (ref "TP6") (pin "1") (pinfunction "1_1") (pintype "passive"))
      (node (ref "U1") (pin "59") (pinfunction "SDATA_59") (pintype "bidirectional"))
    )
    (net (code "37") (name "/SIM_1V8") (class "Default")
      (node (ref "U1") (pin "49") (pinfunction "SIM_1V8_49") (pintype "power_in"))
    )
    (net (code "38") (name "/SIM_CLK") (class "Default")
      (node (ref "U1") (pin "46") (pinfunction "SIM_CLK_46") (pintype "bidirectional"))
    )
    (net (code "39") (name "/SIM_IO") (class "Default")
      (node (ref "U1") (pin "48") (pinfunction "SIM_IO_48") (pintype "bidirectional"))
    )
    (net (code "40") (name "/SIM_RST") (class "Default")
      (node (ref "U1") (pin "43") (pinfunction "SIM_RST_43") (pintype "bidirectional"))
    )
    (net (code "41") (name "/SWDCLK") (class "Default")
      (node (ref "U1") (pin "33") (pinfunction "SWDCLK_33") (pintype "input"))
    )
    (net (code "42") (name "/SWDIO") (class "Default")
      (node (ref "U1") (pin "34") (pinfunction "SWDIO_34") (pintype "bidirectional"))
    )
    (net (code "43") (name "/TXCAN") (class "Default")
      (node (ref "U2") (pin "1") (pinfunction "TXD_1") (pintype "input"))
      (node (ref "U3") (pin "1") (pinfunction "TXCAN_1") (pintype "output"))
    )
    (net (code "44") (name "/USB_CTS") (class "Default")
      (node (ref "U1") (pin "83") (pinfunction "P0.26_83") (pintype "bidirectional"))
    )
    (net (code "45") (name "/USB_RTS") (class "Default")
      (node (ref "U1") (pin "84") (pinfunction "P0.27_84") (pintype "bidirectional"))
    )
    (net (code "46") (name "/USB_RX") (class "Default")
      (node (ref "U1") (pin "87") (pinfunction "P0.29_87") (pintype "bidirectional"))
    )
    (net (code "47") (name "/USB_TX") (class "Default")
      (node (ref "U1") (pin "86") (pinfunction "P0.28_86") (pintype "bidirectional"))
    )
    (net (code "48") (name "/VIO") (class "Default")
      (node (ref "TP4") (pin "1") (pinfunction "1_1") (pintype "passive"))
      (node (ref "U1") (pin "57") (pinfunction "VIO_57") (pintype "power_in"))
    )
    (net (code "49") (name "/nRESET") (class "Default")
      (node (ref "R5") (pin "1") (pinfunction "1_1") (pintype "passive"))
      (node (ref "SW1") (pin "2") (pinfunction "2_2") (pintype "passive"))
    )
    (net (code "53") (name "3V3") (class "Default")
      (node (ref "C13") (pin "2") (pinfunction "2_2") (pintype "passive"))
      (node (ref "L2") (pin "2") (pinfunction "2_2") (pintype "passive"))
    )
    (net (code "54") (name "GND") (class "Default")
      (node (ref "C1") (pin "2") (pinfunction "2_2") (pintype "passive"))
      (node (ref "C10") (pin "2") (pinfunction "2_2") (pintype "passive"))
      (node (ref "C12") (pin "2") (pinfunction "2_2") (pintype "passive"))
      (node (ref "C13") (pin "1") (pinfunction "1_1") (pintype "passive"))
      (node (ref "C15") (pin "2") (pinfunction "2_2") (pintype "passive"))
      (node (ref "C16") (pin "2") (pinfunction "2_2") (pintype "passive"))
      (node (ref "C17") (pin "1") (pinfunction "1_1") (pintype "passive"))
      (node (ref "C18") (pin "1") (pinfunction "1_1") (pintype "passive"))
      (node (ref "C2") (pin "2") (pinfunction "2_2") (pintype "passive"))
      (node (ref "C26") (pin "2") (pinfunction "2_2") (pintype "passive"))
      (node (ref "C27") (pin "2") (pinfunction "2_2") (pintype "passive"))
      (node (ref "C3") (pin "1") (pinfunction "1_1") (pintype "passive"))
      (node (ref "C4") (pin "2") (pinfunction "2_2") (pintype "passive"))
      (node (ref "C5") (pin "2") (pinfunction "2_2") (pintype "passive"))
      (node (ref "C6") (pin "1") (pinfunction "1_1") (pintype "passive"))
      (node (ref "C7") (pin "2") (pinfunction "2_2") (pintype "passive"))
      (node (ref "C8") (pin "2") (pinfunction "2_2") (pintype "passive"))
      (node (ref "C9") (pin "2") (pinfunction "2_2") (pintype "passive"))
      (node (ref "DS1") (pin "2") (pinfunction "K_2") (pintype "passive"))
      (node (ref "DS2") (pin "2") (pinfunction "K_2") (pintype "passive"))
      (node (ref "DS3") (pin "2") (pinfunction "K_2") (pintype "passive"))
      (node (ref "DS4") (pin "2") (pinfunction "K_2") (pintype "passive"))
      (node (ref "DS5") (pin "2") (pinfunction "K_2") (pintype "passive"))
      (node (ref "J1") (pin "2") (pinfunction "2_2") (pintype "passive"))
      (node (ref "J1") (pin "3") (pinfunction "3_3") (pintype "passive"))
      (node (ref "J1") (pin "4") (pinfunction "4_4") (pintype "passive"))
      (node (ref "J1") (pin "5") (pinfunction "5_5") (pintype "passive"))
      (node (ref "J2") (pin "2") (pinfunction "2_2") (pintype "passive"))
      (node (ref "J2") (pin "3") (pinfunction "3_3") (pintype "passive"))
      (node (ref "J2") (pin "4") (pinfunction "4_4") (pintype "passive"))
      (node (ref "J2") (pin "5") (pinfunction "5_5") (pintype "passive"))
      (node (ref "J5") (pin "1") (pinfunction "1_1") (pintype "passive"))
      (node (ref "J5") (pin "2") (pinfunction "2_2") (pintype "passive"))
      (node (ref "J5") (pin "MH1") (pinfunction "MH1_MH1") (pintype "passive"))
      (node (ref "J5") (pin "MH2") (pinfunction "MH2_MH2") (pintype "passive"))
      (node (ref "P4") (pin "2") (pinfunction "2_2") (pintype "passive"))
      (node (ref "P5") (pin "2") (pinfunction "2_2") (pintype "passive"))
      (node (ref "P6") (pin "2") (pinfunction "2_2") (pintype "passive"))
      (node (ref "Q1") (pin "1") (pinfunction "S1_1") (pintype "passive"))
      (node (ref "Q2") (pin "1") (pinfunction "S1_1") (pintype "passive"))
      (node (ref "R13") (pin "2") (pinfunction "2_2") (pintype "passive"))
      (node (ref "R19") (pin "2") (pinfunction "2_2") (pintype "passive"))
      (node (ref "SW1") (pin "3") (pinfunction "3_3") (pintype "passive"))
      (node (ref "SW1") (pin "4") (pinfunction "4_4") (pintype "passive"))
      (node (ref "U1") (pin "1") (pinfunction "GND_1") (pintype "power_in"))
      (node (ref "U1") (pin "103") (pinfunction "GND_103") (pintype "power_in"))
      (node (ref "U1") (pin "11") (pinfunction "GND_11") (pintype "passive"))
      (node (ref "U1") (pin "14") (pinfunction "GND_14") (pintype "power_in"))
      (node (ref "U1") (pin "17") (pinfunction "GND_17") (pintype "power_in"))
      (node (ref "U1") (pin "21") (pinfunction "GND_21") (pintype "power_in"))
      (node (ref "U1") (pin "27") (pinfunction "GND_27") (pintype "power_in"))
      (node (ref "U1") (pin "31") (pinfunction "GND_31") (pintype "power_in"))
      (node (ref "U1") (pin "36") (pinfunction "GND_36") (pintype "power_in"))
      (node (ref "U1") (pin "41") (pinfunction "GND_41") (pintype "power_in"))
      (node (ref "U1") (pin "44") (pinfunction "GND_44") (pintype "power_in"))
      (node (ref "U1") (pin "47") (pinfunction "GND_47") (pintype "power_in"))
      (node (ref "U1") (pin "5") (pinfunction "GND_5") (pintype "power_in"))
      (node (ref "U1") (pin "50") (pinfunction "GND_50") (pintype "power_in"))
      (node (ref "U1") (pin "52") (pinfunction "GND_52") (pintype "power_in"))
      (node (ref "U1") (pin "56") (pinfunction "GND_56") (pintype "power_in"))
      (node (ref "U1") (pin "6") (pinfunction "GND_6") (pintype "passive"))
      (node (ref "U1") (pin "60") (pinfunction "GND_60") (pintype "power_in"))
      (node (ref "U1") (pin "62") (pinfunction "GND_62") (pintype "power_in"))
      (node (ref "U1") (pin "63") (pinfunction "GND_63") (pintype "power_in"))
      (node (ref "U1") (pin "65") (pinfunction "GND_65") (pintype "power_in"))
      (node (ref "U1") (pin "66") (pinfunction "GND_66") (pintype "power_in"))
      (node (ref "U1") (pin "68") (pinfunction "GND_68") (pintype "passive"))
      (node (ref "U1") (pin "69") (pinfunction "GND_69") (pintype "passive"))
      (node (ref "U1") (pin "7") (pinfunction "GND_7") (pintype "passive"))
      (node (ref "U1") (pin "72") (pinfunction "GND_72") (pintype "power_in"))
      (node (ref "U1") (pin "74") (pinfunction "GND_74") (pintype "power_in"))
      (node (ref "U1") (pin "75") (pinfunction "GND_75") (pintype "power_in"))
      (node (ref "U1") (pin "76") (pinfunction "GND_76") (pintype "power_in"))
      (node (ref "U1") (pin "77") (pinfunction "GND_77") (pintype "power_in"))
      (node (ref "U1") (pin "78") (pinfunction "GND_78") (pintype "power_in"))
      (node (ref "U1") (pin "79") (pinfunction "GND_79") (pintype "power_in"))
      (node (ref "U1") (pin "8") (pinfunction "GND_8") (pintype "passive"))
      (node (ref "U1") (pin "80") (pinfunction "GND_80") (pintype "power_in"))
      (node (ref "U1") (pin "81") (pinfunction "GND_81") (pintype "power_in"))
      (node (ref "U1") (pin "82") (pinfunction "GND_82") (pintype "power_in"))
      (node (ref "U1") (pin "85") (pinfunction "GND_85") (pintype "power_in"))
      (node (ref "U1") (pin "9") (pinfunction "GND_9") (pintype "power_in"))
      (node (ref "U1") (pin "90") (pinfunction "GND_90") (pintype "power_in"))
      (node (ref "U1") (pin "94") (pinfunction "GND_94") (pintype "power_in"))
      (node (ref "U1") (pin "98") (pinfunction "GND_98") (pintype "power_in"))
      (node (ref "U2") (pin "2") (pinfunction "GND_2") (pintype "power_in"))
      (node (ref "U2") (pin "5") (pinfunction "SHDN_5") (pintype "input"))
      (node (ref "U2") (pin "8") (pinfunction "S_8") (pintype "input"))
      (node (ref "U3") (pin "9") (pinfunction "VSS_9") (pintype "power_in"))
      (node (ref "U4") (pin "1") (pinfunction "SDO/SA0_1") (pintype "output"))
      (node (ref "U4") (pin "2") (pinfunction "SDx_2") (pintype "passive"))
      (node (ref "U4") (pin "3") (pinfunction "SCx_3") (pintype "passive"))
      (node (ref "U4") (pin "6") (pinfunction "GND_6") (pintype "power_in"))
      (node (ref "U4") (pin "7") (pinfunction "GND_7") (pintype "power_in"))
    )
    (net (code "55") (name "Net-(C12-Pad1)") (class "Default")
      (node (ref "C12") (pin "1") (pinfunction "1_1") (pintype "passive"))
      (node (ref "L1") (pin "1") (pinfunction "1_1") (pintype "passive"))
    )
    (net (code "56") (name "Net-(DS1-A)") (class "Default")
      (node (ref "DS1") (pin "1") (pinfunction "A_1") (pintype "passive"))
      (node (ref "R2") (pin "1") (pinfunction "1_1") (pintype "passive"))
    )
    (net (code "57") (name "Net-(DS2-A)") (class "Default")
      (node (ref "DS2") (pin "1") (pinfunction "A_1") (pintype "passive"))
      (node (ref "R4") (pin "1") (pinfunction "1_1") (pintype "passive"))
    )
    (net (code "58") (name "Net-(DS3-A)") (class "Default")
      (node (ref "DS3") (pin "1") (pinfunction "A_1") (pintype "passive"))
      (node (ref "R6") (pin "1") (pinfunction "1_1") (pintype "passive"))
    )
    (net (code "59") (name "Net-(DS4-A)") (class "Default")
      (node (ref "DS4") (pin "1") (pinfunction "A_1") (pintype "passive"))
      (node (ref "R7") (pin "1") (pinfunction "1_1") (pintype "passive"))
    )
    (net (code "60") (name "Net-(DS5-A)") (class "Default")
      (node (ref "DS5") (pin "1") (pinfunction "A_1") (pintype "passive"))
      (node (ref "R8") (pin "1") (pinfunction "1_1") (pintype "passive"))
    )
    (net (code "61") (name "Net-(Q1A-D1)") (class "Default")
      (node (ref "Q1") (pin "3") (pinfunction "D2_3") (pintype "passive"))
      (node (ref "Q1") (pin "6") (pinfunction "D1_6") (pintype "passive"))
      (node (ref "Q2") (pin "2") (pinfunction "G1_2") (pintype "passive"))
    )
    (net (code "62") (name "Net-(Q1B-S2)") (class "Default")
      (node (ref "Q1") (pin "4") (pinfunction "S2_4") (pintype "passive"))
      (node (ref "R10") (pin "1") (pinfunction "1_1") (pintype "passive"))
      (node (ref "R9") (pin "2") (pinfunction "2_2") (pintype "passive"))
    )
    (net (code "63") (name "Net-(Q2A-D1)") (class "Default")
      (node (ref "Q2") (pin "6") (pinfunction "D1_6") (pintype "passive"))
      (node (ref "SW1") (pin "1") (pinfunction "1_1") (pintype "passive"))
    )
    (net (code "64") (name "Net-(R13-Pad1)") (class "Default")
      (node (ref "R13") (pin "1") (pinfunction "1_1") (pintype "passive"))
      (node (ref "SW3") (pin "4") (pinfunction "4_4") (pintype "passive"))
    )
    (net (code "65") (name "Net-(R19-Pad1)") (class "Default")
      (node (ref "R19") (pin "1") (pinfunction "1_1") (pintype "passive"))
      (node (ref "SW2") (pin "4") (pinfunction "4_4") (pintype "passive"))
    )
    (net (code "66") (name "Net-(U1A-ENABLE)") (class "Default")
      (node (ref "R3") (pin "1") (pinfunction "1_1") (pintype "passive"))
      (node (ref "U1") (pin "101") (pinfunction "ENABLE_101") (pintype "input"))
    )
    (net (code "67") (name "Net-(U1A-VDD1)") (class "Default")
      (node (ref "FB1") (pin "2") (pinfunction "2_2") (pintype "passive"))
      (node (ref "R3") (pin "2") (pinfunction "2_2") (pintype "passive"))
      (node (ref "U1") (pin "102") (pinfunction "VDD1_102") (pintype "power_in"))
    )
    (net (code "68") (name "Net-(U1A-VDD2)") (class "Default")
      (node (ref "C6") (pin "2") (pinfunction "2_2") (pintype "passive"))
      (node (ref "C8") (pin "1") (pinfunction "1_1") (pintype "passive"))
      (node (ref "C9") (pin "1") (pinfunction "1_1") (pintype "passive"))
      (node (ref "R1") (pin "2") (pinfunction "2_2") (pintype "passive"))
      (node (ref "U1") (pin "22") (pinfunction "VDD2_22") (pintype "power_in"))
    )
    (net (code "69") (name "Net-(U1A-nRESET)") (class "Default")
      (node (ref "C10") (pin "1") (pinfunction "1_1") (pintype "passive"))
      (node (ref "R5") (pin "2") (pinfunction "2_2") (pintype "passive"))
      (node (ref "U1") (pin "32") (pinfunction "nRESET_32") (pintype "input"))
    )
    (net (code "70") (name "Net-(U3-OSC1)") (class "Default")
      (node (ref "C18") (pin "2") (pinfunction "2_2") (pintype "passive"))
      (node (ref "U3") (pin "8") (pinfunction "OSC1_8") (pintype "input"))
      (node (ref "Y1") (pin "2") (pinfunction "2_2") (pintype "passive"))
    )
    (net (code "71") (name "Net-(U3-OSC2)") (class "Default")
      (node (ref "C17") (pin "2") (pinfunction "2_2") (pintype "passive"))
      (node (ref "U3") (pin "7") (pinfunction "OSC2_7") (pintype "input"))
      (node (ref "Y1") (pin "1") (pinfunction "1_1") (pintype "passive"))
    )
    (net (code "72") (name "Net-(U3-~{RESET})") (class "Default")
      (node (ref "R14") (pin "1") (pinfunction "1_1") (pintype "passive"))
      (node (ref "U3") (pin "17") (pinfunction "~{RESET}_17") (pintype "input"))
    )
    (net (code "73") (name "OBD_12V") (class "Default")
      (node (ref "J5") (pin "9") (pinfunction "9_9") (pintype "passive"))
    )
    (net (code "74") (name "VDD") (class "Default")
      (node (ref "C1") (pin "1") (pinfunction "1_1") (pintype "passive"))
      (node (ref "C15") (pin "1") (pinfunction "1_1") (pintype "passive"))
      (node (ref "C16") (pin "1") (pinfunction "1_1") (pintype "passive"))
      (node (ref "C2") (pin "1") (pinfunction "1_1") (pintype "passive"))
      (node (ref "C26") (pin "1") (pinfunction "1_1") (pintype "passive"))
      (node (ref "C27") (pin "1") (pinfunction "1_1") (pintype "passive"))
      (node (ref "P4") (pin "8") (pinfunction "8_8") (pintype "passive"))
      (node (ref "P6") (pin "1") (pinfunction "1_1") (pintype "passive"))
      (node (ref "R10") (pin "2") (pinfunction "2_2") (pintype "passive"))
      (node (ref "R11") (pin "1") (pinfunction "1_1") (pintype "passive"))
      (node (ref "R14") (pin "2") (pinfunction "2_2") (pintype "passive"))
      (node (ref "R16") (pin "2") (pinfunction "2_2") (pintype "passive"))
      (node (ref "R18") (pin "2") (pinfunction "2_2") (pintype "passive"))
      (node (ref "SW2") (pin "1") (pinfunction "1_1") (pintype "passive"))
      (node (ref "SW2") (pin "2") (pinfunction "2_2") (pintype "passive"))
      (node (ref "SW3") (pin "1") (pinfunction "1_1") (pintype "passive"))
      (node (ref "SW3") (pin "2") (pinfunction "2_2") (pintype "passive"))
      (node (ref "TP10") (pin "1") (pinfunction "1_1") (pintype "passive"))
      (node (ref "TP11") (pin "1") (pinfunction "1_1") (pintype "passive"))
      (node (ref "TP9") (pin "1") (pinfunction "1_1") (pintype "passive"))
      (node (ref "U1") (pin "12") (pinfunction "VDD_GPIO_12") (pintype "power_in"))
      (node (ref "U2") (pin "3") (pinfunction "VCC_3") (pintype "power_in"))
      (node (ref "U3") (pin "18") (pinfunction "VDD_18") (pintype "power_in"))
      (node (ref "U4") (pin "12") (pinfunction "CS_12") (pintype "input"))
      (node (ref "U4") (pin "5") (pinfunction "VDDIO_5") (pintype "power_in"))
      (node (ref "U4") (pin "8") (pinfunction "VDD_8") (pintype "power_in"))
    )
    (net (code "75") (name "VSUPPLY") (class "Default")
      (node (ref "C3") (pin "2") (pinfunction "2_2") (pintype "passive"))
      (node (ref "C5") (pin "1") (pinfunction "1_1") (pintype "passive"))
      (node (ref "C7") (pin "1") (pinfunction "1_1") (pintype "passive"))
      (node (ref "FB1") (pin "1") (pinfunction "1_1") (pintype "passive"))
      (node (ref "P5") (pin "1") (pinfunction "1_1") (pintype "passive"))
      (node (ref "R1") (pin "1") (pinfunction "1_1") (pintype "passive"))
    )
    (net (code "76") (name "unconnected-(J5-Pad4)") (class "Default")
      (node (ref "J5") (pin "4") (pinfunction "4_4") (pintype "passive+no_connect"))
    )
    (net (code "77") (name "unconnected-(J5-Pad6)") (class "Default")
      (node (ref "J5") (pin "6") (pinfunction "6_6") (pintype "passive+no_connect"))
    )
    (net (code "78") (name "unconnected-(J5-Pad7)") (class "Default")
      (node (ref "J5") (pin "7") (pinfunction "7_7") (pintype "passive+no_connect"))
    )
    (net (code "79") (name "unconnected-(J5-Pad8)") (class "Default")
      (node (ref "J5") (pin "8") (pinfunction "8_8") (pintype "passive+no_connect"))
    )
    (net (code "80") (name "unconnected-(P4-Pad1)") (class "Default")
      (node (ref "P4") (pin "1") (pinfunction "1_1") (pintype "passive+no_connect"))
    )
    (net (code "81") (name "unconnected-(U1A-AUX-Pad64)") (class "Default")
      (node (ref "U1") (pin "64") (pinfunction "AUX_64") (pintype "bidirectional+no_connect"))
    )
    (net (code "82") (name "unconnected-(U1A-COEX0-Pad93)") (class "Default")
      (node (ref "U1") (pin "93") (pinfunction "COEX0_93") (pintype "bidirectional+no_connect"))
    )
    (net (code "83") (name "unconnected-(U1A-COEX1-Pad92)") (class "Default")
      (node (ref "U1") (pin "92") (pinfunction "COEX1_92") (pintype "bidirectional+no_connect"))
    )
    (net (code "84") (name "unconnected-(U1A-COEX2-Pad91)") (class "Default")
      (node (ref "U1") (pin "91") (pinfunction "COEX2_91") (pintype "bidirectional+no_connect"))
    )
    (net (code "85") (name "unconnected-(U1A-P0.05-Pad2)") (class "Default")
      (node (ref "U1") (pin "2") (pinfunction "P0.05_2") (pintype "bidirectional+no_connect"))
    )
    (net (code "86") (name "unconnected-(U1A-P0.06-Pad3)") (class "Default")
      (node (ref "U1") (pin "3") (pinfunction "P0.06_3") (pintype "bidirectional+no_connect"))
    )
    (net (code "87") (name "unconnected-(U1A-P0.07-Pad4)") (class "Default")
      (node (ref "U1") (pin "4") (pinfunction "P0.07_4") (pintype "bidirectional+no_connect"))
    )
    (net (code "88") (name "unconnected-(U1A-P0.18-Pad29)") (class "Default")
      (node (ref "U1") (pin "29") (pinfunction "P0.18_29") (pintype "bidirectional+no_connect"))
    )
    (net (code "89") (name "unconnected-(U1A-P0.19-Pad30)") (class "Default")
      (node (ref "U1") (pin "30") (pinfunction "P0.19_30") (pintype "bidirectional+no_connect"))
    )
    (net (code "90") (name "unconnected-(U1A-P0.20-Pad35)") (class "Default")
      (node (ref "U1") (pin "35") (pinfunction "P0.20_35") (pintype "bidirectional+no_connect"))
    )
    (net (code "91") (name "unconnected-(U1A-P0.21-Pad37)") (class "Default")
      (node (ref "U1") (pin "37") (pinfunction "P0.21_37") (pintype "bidirectional+no_connect"))
    )
    (net (code "92") (name "unconnected-(U1A-P0.25-Pad42)") (class "Default")
      (node (ref "U1") (pin "42") (pinfunction "P0.25_42") (pintype "bidirectional+no_connect"))
    )
    (net (code "93") (name "unconnected-(U1A-SIM_DET-Pad45)") (class "Default")
      (node (ref "U1") (pin "45") (pinfunction "SIM_DET_45") (pintype "bidirectional+no_connect"))
    )
    (net (code "94") (name "unconnected-(U1B-RES-Pad10)") (class "Default")
      (node (ref "U1") (pin "10") (pinfunction "RES_10") (pintype "passive+no_connect"))
    )
    (net (code "95") (name "unconnected-(U1B-RES-Pad51)") (class "Default")
      (node (ref "U1") (pin "51") (pinfunction "RES_51") (pintype "passive+no_connect"))
    )
    (net (code "96") (name "unconnected-(U1B-RES-Pad70)") (class "Default")
      (node (ref "U1") (pin "70") (pinfunction "RES_70") (pintype "passive+no_connect"))
    )
    (net (code "97") (name "unconnected-(U1B-RES-Pad71)") (class "Default")
      (node (ref "U1") (pin "71") (pinfunction "RES_71") (pintype "passive+no_connect"))
    )
    (net (code "98") (name "unconnected-(U1B-RES-Pad73)") (class "Default")
      (node (ref "U1") (pin "73") (pinfunction "RES_73") (pintype "passive+no_connect"))
    )
    (net (code "99") (name "unconnected-(U1B-RES-Pad104)") (class "Default")
      (node (ref "U1") (pin "104") (pinfunction "RES_104") (pintype "passive+no_connect"))
    )
    (net (code "100") (name "unconnected-(U1B-RES-Pad105)") (class "Default")
      (node (ref "U1") (pin "105") (pinfunction "RES_105") (pintype "passive+no_connect"))
    )
    (net (code "101") (name "unconnected-(U1B-RES-Pad106)") (class "Default")
      (node (ref "U1") (pin "106") (pinfunction "RES_106") (pintype "passive+no_connect"))
    )
    (net (code "102") (name "unconnected-(U1B-RES-Pad107)") (class "Default")
      (node (ref "U1") (pin "107") (pinfunction "RES_107") (pintype "passive+no_connect"))
    )
    (net (code "103") (name "unconnected-(U1B-RES-Pad108)") (class "Default")
      (node (ref "U1") (pin "108") (pinfunction "RES_108") (pintype "passive+no_connect"))
    )
    (net (code "104") (name "unconnected-(U1B-RES-Pad109)") (class "Default")
      (node (ref "U1") (pin "109") (pinfunction "RES_109") (pintype "passive+no_connect"))
    )
    (net (code "105") (name "unconnected-(U1B-RES-Pad110)") (class "Default")
      (node (ref "U1") (pin "110") (pinfunction "RES_110") (pintype "passive+no_connect"))
    )
    (net (code "106") (name "unconnected-(U1B-RES-Pad111)") (class "Default")
      (node (ref "U1") (pin "111") (pinfunction "RES_111") (pintype "passive+no_connect"))
    )
    (net (code "107") (name "unconnected-(U1B-RES-Pad112)") (class "Default")
      (node (ref "U1") (pin "112") (pinfunction "RES_112") (pintype "passive+no_connect"))
    )
    (net (code "108") (name "unconnected-(U1B-RES-Pad113)") (class "Default")
      (node (ref "U1") (pin "113") (pinfunction "RES_113") (pintype "passive+no_connect"))
    )
    (net (code "109") (name "unconnected-(U1B-RES-Pad114)") (class "Default")
      (node (ref "U1") (pin "114") (pinfunction "RES_114") (pintype "passive+no_connect"))
    )
    (net (code "110") (name "unconnected-(U1B-RES-Pad115)") (class "Default")
      (node (ref "U1") (pin "115") (pinfunction "RES_115") (pintype "passive+no_connect"))
    )
    (net (code "111") (name "unconnected-(U1B-RES-Pad116)") (class "Default")
      (node (ref "U1") (pin "116") (pinfunction "RES_116") (pintype "passive+no_connect"))
    )
    (net (code "112") (name "unconnected-(U1B-RES-Pad117)") (class "Default")
      (node (ref "U1") (pin "117") (pinfunction "RES_117") (pintype "passive+no_connect"))
    )
    (net (code "113") (name "unconnected-(U1B-RES-Pad118)") (class "Default")
      (node (ref "U1") (pin "118") (pinfunction "RES_118") (pintype "passive+no_connect"))
    )
    (net (code "114") (name "unconnected-(U1B-RES-Pad119)") (class "Default")
      (node (ref "U1") (pin "119") (pinfunction "RES_119") (pintype "passive+no_connect"))
    )
    (net (code "115") (name "unconnected-(U1B-RES-Pad120)") (class "Default")
      (node (ref "U1") (pin "120") (pinfunction "RES_120") (pintype "passive+no_connect"))
    )
    (net (code "116") (name "unconnected-(U1B-RES-Pad121)") (class "Default")
      (node (ref "U1") (pin "121") (pinfunction "RES_121") (pintype "passive+no_connect"))
    )
    (net (code "117") (name "unconnected-(U1B-RES-Pad122)") (class "Default")
      (node (ref "U1") (pin "122") (pinfunction "RES_122") (pintype "passive+no_connect"))
    )
    (net (code "118") (name "unconnected-(U1B-RES-Pad123)") (class "Default")
      (node (ref "U1") (pin "123") (pinfunction "RES_123") (pintype "passive+no_connect"))
    )
    (net (code "119") (name "unconnected-(U1B-RES-Pad124)") (class "Default")
      (node (ref "U1") (pin "124") (pinfunction "RES_124") (pintype "passive+no_connect"))
    )
    (net (code "120") (name "unconnected-(U1B-RES-Pad125)") (class "Default")
      (node (ref "U1") (pin "125") (pinfunction "RES_125") (pintype "passive+no_connect"))
    )
    (net (code "121") (name "unconnected-(U1B-RES-Pad126)") (class "Default")
      (node (ref "U1") (pin "126") (pinfunction "RES_126") (pintype "passive+no_connect"))
    )
    (net (code "122") (name "unconnected-(U1B-RES-Pad127)") (class "Default")
      (node (ref "U1") (pin "127") (pinfunction "RES_127") (pintype "passive+no_connect"))
    )
    (net (code "123") (name "unconnected-(U3-CLKOUT{slash}SOF-Pad3)") (class "Default")
      (node (ref "U3") (pin "3") (pinfunction "CLKOUT/SOF_3") (pintype "output+no_connect"))
    )
    (net (code "124") (name "unconnected-(U3-~{RX0BF}-Pad11)") (class "Default")
      (node (ref "U3") (pin "11") (pinfunction "~{RX0BF}_11") (pintype "input+no_connect"))
    )
    (net (code "125") (name "unconnected-(U3-~{RX1BF}-Pad10)") (class "Default")
      (node (ref "U3") (pin "10") (pinfunction "~{RX1BF}_10") (pintype "input+no_connect"))
    )
    (net (code "126") (name "unconnected-(U3-~{TX0RTS}-Pad4)") (class "Default")
      (node (ref "U3") (pin "4") (pinfunction "~{TX0RTS}_4") (pintype "output+no_connect"))
    )
    (net (code "127") (name "unconnected-(U3-~{TX1RTS}-Pad5)") (class "Default")
      (node (ref "U3") (pin "5") (pinfunction "~{TX1RTS}_5") (pintype "output+no_connect"))
    )
    (net (code "128") (name "unconnected-(U3-~{TX2RTS}-Pad6)") (class "Default")
      (node (ref "U3") (pin "6") (pinfunction "~{TX2RTS}_6") (pintype "output+no_connect"))
    )
    (net (code "129") (name "unconnected-(U4-INT2-Pad9)") (class "Default")
      (node (ref "U4") (pin "9") (pinfunction "INT2_9") (pintype "input+no_connect"))
    )
    (net (code "130") (name "unconnected-(U4-NC-Pad10)") (class "Default")
      (node (ref "U4") (pin "10") (pinfunction "NC_10") (pintype "passive+no_connect"))
    )
    (net (code "131") (name "unconnected-(U4-NC-Pad11)") (class "Default")
      (node (ref "U4") (pin "11") (pinfunction "NC_11") (pintype "passive+no_connect"))
    )
  )
)
